# US_IF.net
KiCad netlist of a schematic drawn in Altium Designer
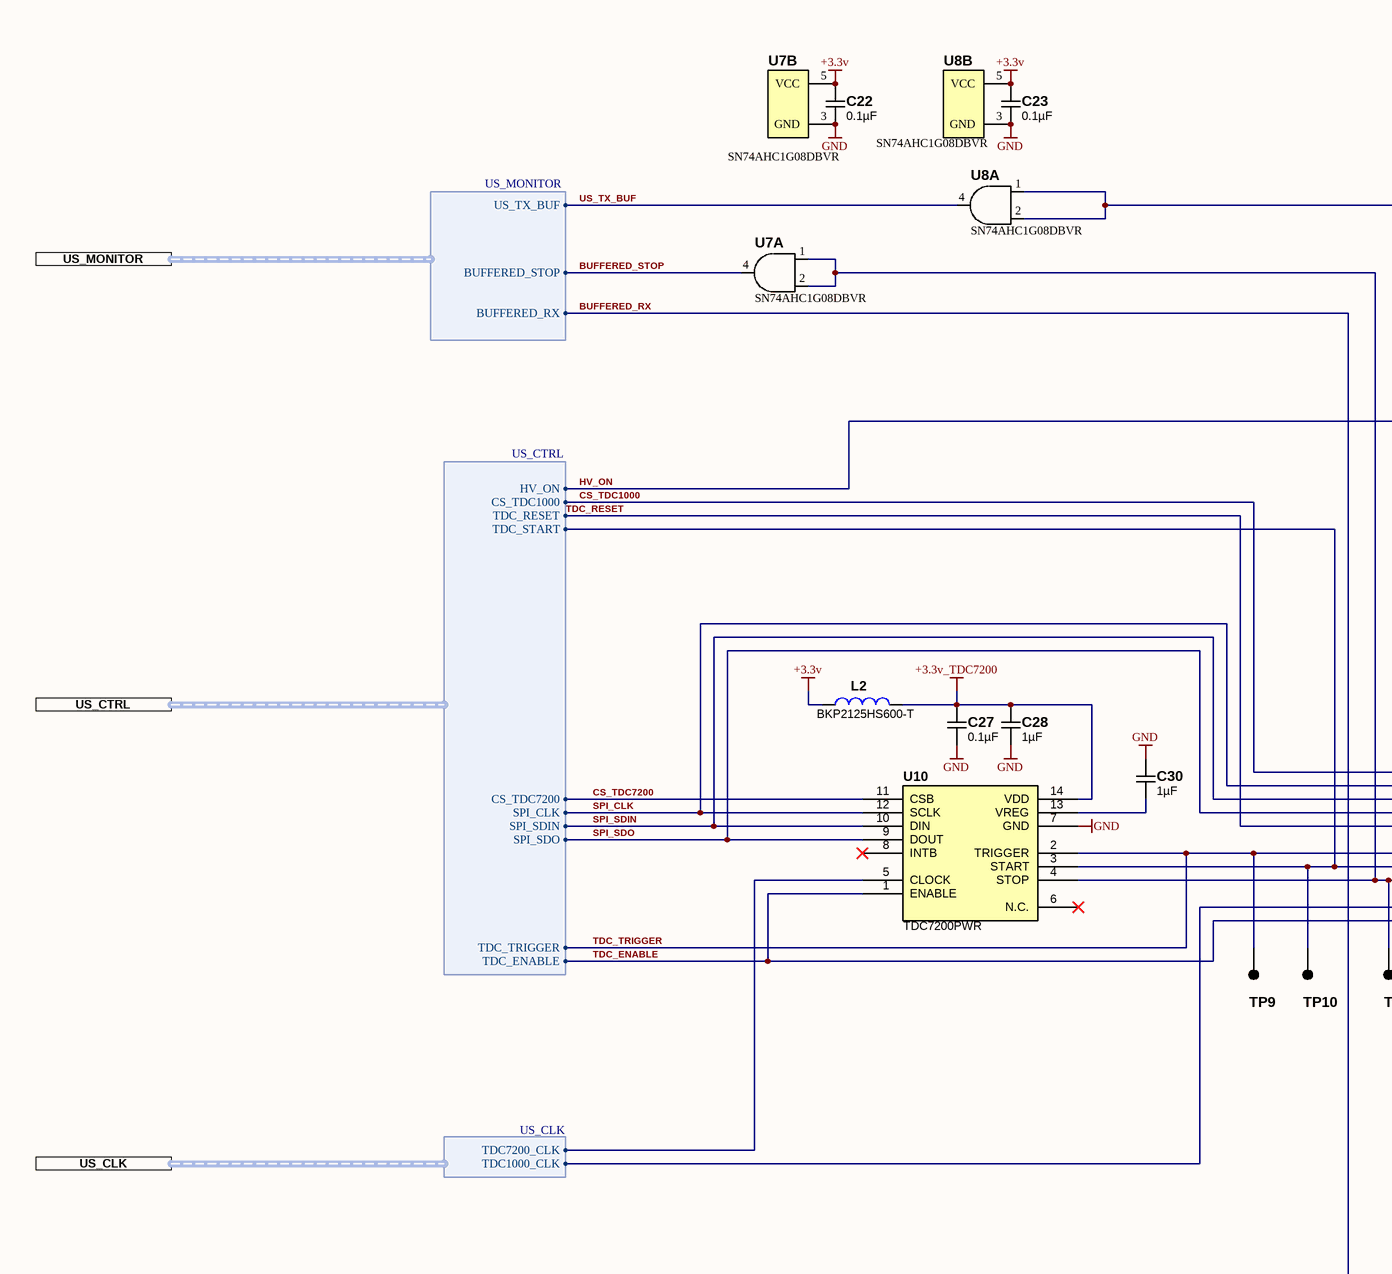
[diagram p0: US_IF.SchDoc, left]
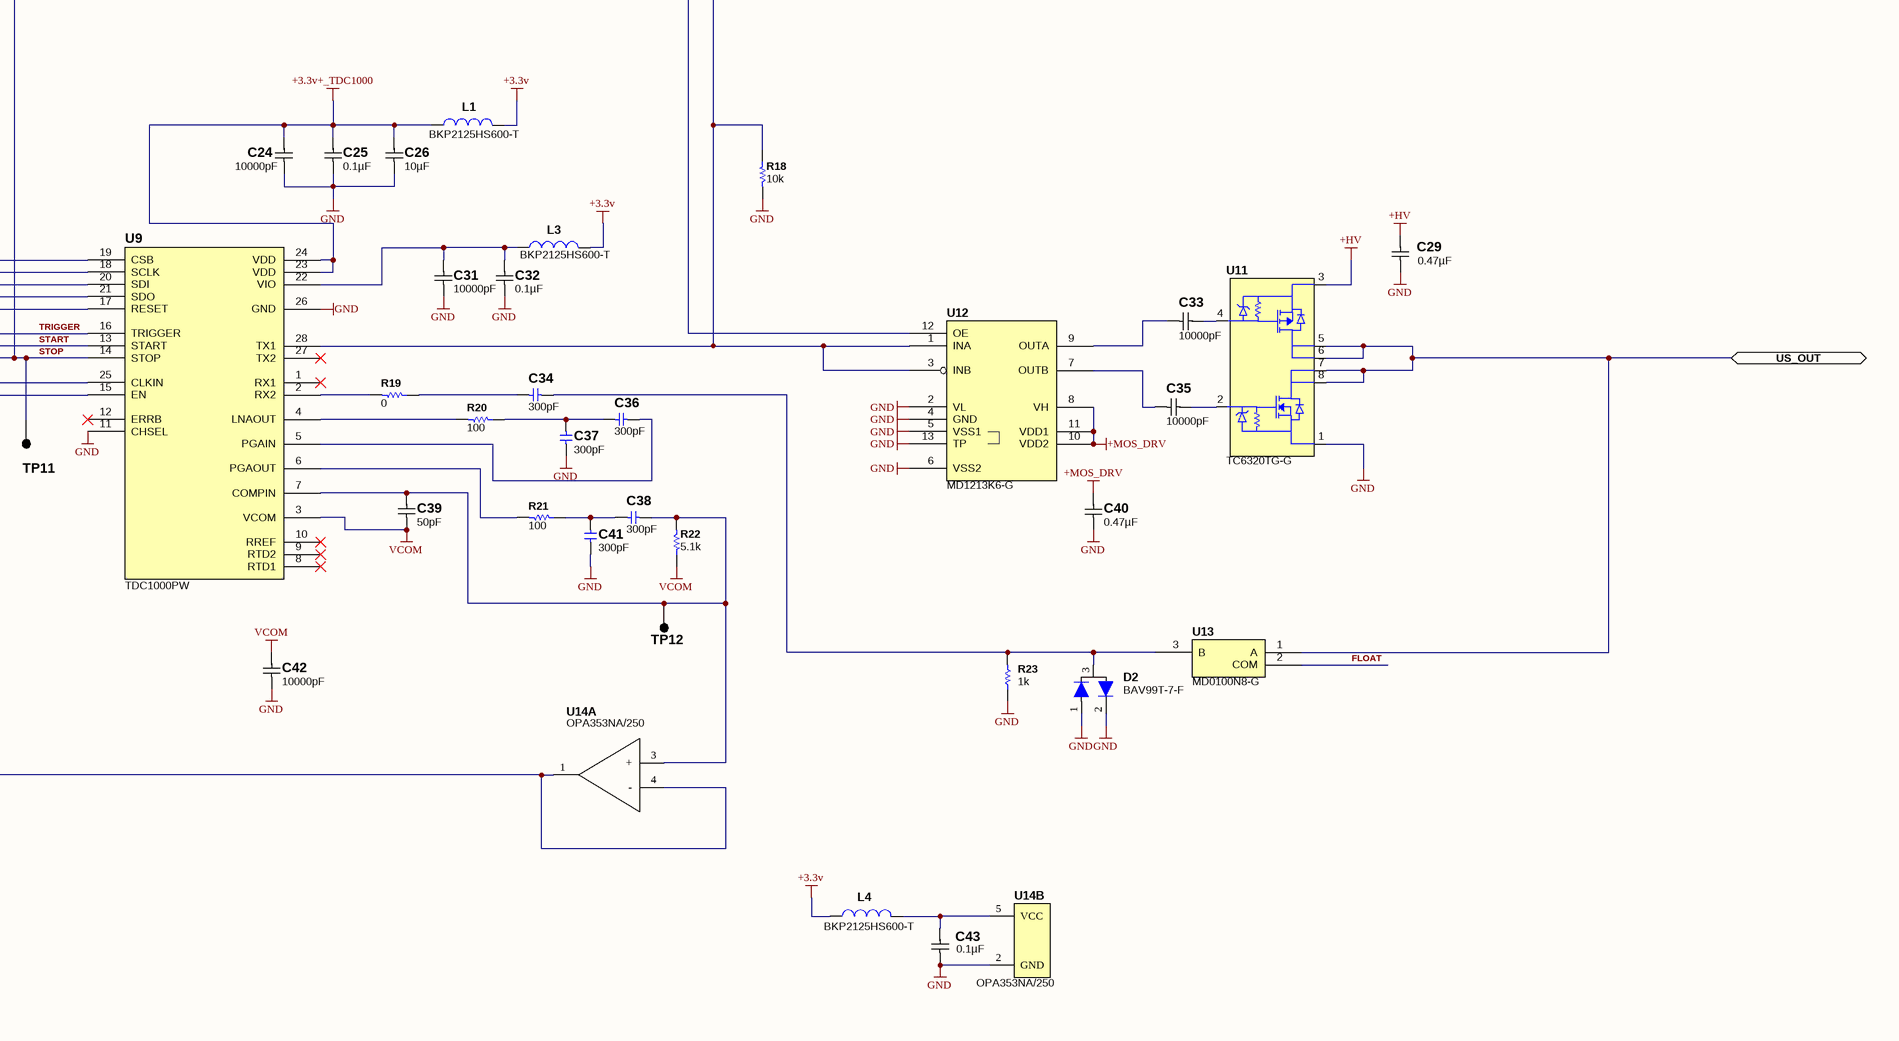
[diagram p1: US_IF.SchDoc, right]

(export (version "E")
  (design (tool "Eeschema 10.0.6"))
  (components
    (comp (ref "C22")
      (value "0.1µF")
      (footprint "C0603_0.90MM_HD")
      (description "CAP CER 0.1UF 50V X7R 0603")
      (fields
        (field (name "MANUFACTURER PART NUMBER") "CGA3E2X7R1H104K080AE")
        (field (name "MANUFACTURER") "TDK Corporation")
      )
      (libsource (lib "Capacitors - TDK- AEC-Q200") (part "C_2P_NP"))
    )
    (comp (ref "C23")
      (value "0.1µF")
      (footprint "C0603_0.90MM_HD")
      (description "CAP CER 0.1UF 50V X7R 0603")
      (fields
        (field (name "MANUFACTURER PART NUMBER") "CGA3E2X7R1H104K080AE")
        (field (name "MANUFACTURER") "TDK Corporation")
      )
      (libsource (lib "Capacitors - TDK- AEC-Q200") (part "C_2P_NP"))
    )
    (comp (ref "C24")
      (value "10000pF")
      (footprint "C0603_0.95MM_HD")
      (description "CAP CER 10000PF 100V C0GNP0 0603")
      (fields
        (field (name "MANUFACTURER PART NUMBER") "CGA3E1C0G2A103J080AE")
        (field (name "MANUFACTURER") "TDK Corporation")
      )
      (libsource (lib "Capacitors - TDK- AEC-Q200") (part "C_2P_NP"))
    )
    (comp (ref "C25")
      (value "0.1µF")
      (footprint "C0603_0.90MM_HD")
      (description "CAP CER 0.1UF 50V X7R 0603")
      (fields
        (field (name "MANUFACTURER PART NUMBER") "CGA3E2X7R1H104K080AE")
        (field (name "MANUFACTURER") "TDK Corporation")
      )
      (libsource (lib "Capacitors - TDK- AEC-Q200") (part "C_2P_NP"))
    )
    (comp (ref "C26")
      (value "10µF")
      (footprint "C0805_1.45MM_HD")
      (description "CAP CER 10UF 6.3V X7R 0805")
      (fields
        (field (name "MANUFACTURER PART NUMBER") "CGA4J1X7R0J106K125AC")
        (field (name "MANUFACTURER") "TDK Corporation")
      )
      (libsource (lib "Capacitors - TDK- AEC-Q200") (part "C_2P_NP"))
    )
    (comp (ref "C27")
      (value "0.1µF")
      (footprint "C0603_0.90MM_HD")
      (description "CAP CER 0.1UF 50V X7R 0603")
      (fields
        (field (name "MANUFACTURER PART NUMBER") "CGA3E2X7R1H104K080AE")
        (field (name "MANUFACTURER") "TDK Corporation")
      )
      (libsource (lib "Capacitors - TDK- AEC-Q200") (part "C_2P_NP"))
    )
    (comp (ref "C28")
      (value "1µF")
      (footprint "C0603_0.95MM_HD")
      (description "CAP CER 1UF 25V X7R 0603")
      (fields
        (field (name "MANUFACTURER PART NUMBER") "CGA3E1X7R1E105K080AE")
        (field (name "MANUFACTURER") "TDK Corporation")
      )
      (libsource (lib "Capacitors - TDK- AEC-Q200") (part "C_2P_NP"))
    )
    (comp (ref "C29")
      (value "0.47µF")
      (footprint "C0805_1.45MM_HD")
      (description "CAP CER 0.47UF 50V X7R 0805")
      (fields
        (field (name "MANUFACTURER PART NUMBER") "CGA4J3X7R1H474K125AE")
        (field (name "MANUFACTURER") "TDK Corporation")
      )
      (libsource (lib "Capacitors - TDK- AEC-Q200") (part "C_2P_NP"))
    )
    (comp (ref "C30")
      (value "1µF")
      (footprint "C0603_0.95MM_HD")
      (description "CAP CER 1UF 25V X7R 0603")
      (fields
        (field (name "MANUFACTURER PART NUMBER") "CGA3E1X7R1E105K080AE")
        (field (name "MANUFACTURER") "TDK Corporation")
      )
      (libsource (lib "Capacitors - TDK- AEC-Q200") (part "C_2P_NP"))
    )
    (comp (ref "C31")
      (value "10000pF")
      (footprint "C0603_0.90MM_HD")
      (description "CAP CER 10000PF 50V X7R 0603")
      (fields
        (field (name "MANUFACTURER PART NUMBER") "CGA3E2X7R1H103M080AE")
        (field (name "MANUFACTURER") "TDK Corporation")
      )
      (libsource (lib "Capacitors - TDK- AEC-Q200") (part "C_2P_NP"))
    )
    (comp (ref "C32")
      (value "0.1µF")
      (footprint "C0603_0.90MM_HD")
      (description "CAP CER 0.1UF 50V X7R 0603")
      (fields
        (field (name "MANUFACTURER PART NUMBER") "CGA3E2X7R1H104K080AE")
        (field (name "MANUFACTURER") "TDK Corporation")
      )
      (libsource (lib "Capacitors - TDK- AEC-Q200") (part "C_2P_NP"))
    )
    (comp (ref "C33")
      (value "10000pF")
      (footprint "C0603_0.95MM_HD")
      (description "CAP CER 10000PF 100V C0GNP0 0603")
      (fields
        (field (name "MANUFACTURER PART NUMBER") "CGA3E1C0G2A103J080AE")
        (field (name "MANUFACTURER") "TDK Corporation")
      )
      (libsource (lib "Capacitors - TDK- AEC-Q200") (part "C_2P_NP"))
    )
    (comp (ref "C34")
      (value "300pF")
      (footprint "C0603_0.90mm_MD")
      (description "Cap Ceramic 300pF 50V C0G 5% SMD 0603 125C Paper T/R")
      (fields
        (field (name "MANUFACTURER PART NUMBER") "CL10C301JB8NNNC")
        (field (name "MANUFACTURER") "Samsung")
      )
      (libsource (lib "eCapacitors") (part "CL10C301JB8NNNC"))
    )
    (comp (ref "C35")
      (value "10000pF")
      (footprint "C0603_0.95MM_HD")
      (description "CAP CER 10000PF 100V C0GNP0 0603")
      (fields
        (field (name "MANUFACTURER PART NUMBER") "CGA3E1C0G2A103J080AE")
        (field (name "MANUFACTURER") "TDK Corporation")
      )
      (libsource (lib "Capacitors - TDK- AEC-Q200") (part "C_2P_NP"))
    )
    (comp (ref "C36")
      (value "300pF")
      (footprint "C0603_0.90mm_MD")
      (description "Cap Ceramic 300pF 50V C0G 5% SMD 0603 125C Paper T/R")
      (fields
        (field (name "MANUFACTURER PART NUMBER") "CL10C301JB8NNNC")
        (field (name "MANUFACTURER") "Samsung")
      )
      (libsource (lib "eCapacitors") (part "CL10C301JB8NNNC"))
    )
    (comp (ref "C37")
      (value "300pF")
      (footprint "C0603_0.90mm_MD")
      (description "Cap Ceramic 300pF 50V C0G 5% SMD 0603 125C Paper T/R")
      (fields
        (field (name "MANUFACTURER PART NUMBER") "CL10C301JB8NNNC")
        (field (name "MANUFACTURER") "Samsung")
      )
      (libsource (lib "eCapacitors") (part "CL10C301JB8NNNC"))
    )
    (comp (ref "C38")
      (value "300pF")
      (footprint "C0603_0.90mm_MD")
      (description "Cap Ceramic 300pF 50V C0G 5% SMD 0603 125C Paper T/R")
      (fields
        (field (name "MANUFACTURER PART NUMBER") "CL10C301JB8NNNC")
        (field (name "MANUFACTURER") "Samsung")
      )
      (libsource (lib "eCapacitors") (part "CL10C301JB8NNNC"))
    )
    (comp (ref "C39")
      (value "50pF")
      (footprint "C0603_0.90MM_HD")
      (description "CAP CER 50PF 100V C0G/NP0 0603")
      (fields
        (field (name "MANUFACTURER PART NUMBER") "CL10C500JC81PNC")
        (field (name "MANUFACTURER") "Samsung Electro-Mechanics")
      )
      (libsource (lib "Capacitors - Samsung - AEC-Q200") (part "C_2P_NP"))
    )
    (comp (ref "C40")
      (value "0.47µF")
      (footprint "C0805_1.45MM_HD")
      (description "CAP CER 0.47UF 50V X7R 0805")
      (fields
        (field (name "MANUFACTURER PART NUMBER") "CGA4J3X7R1H474K125AE")
        (field (name "MANUFACTURER") "TDK Corporation")
      )
      (libsource (lib "Capacitors - TDK- AEC-Q200") (part "C_2P_NP"))
    )
    (comp (ref "C41")
      (value "300pF")
      (footprint "C0603_0.90mm_MD")
      (description "Cap Ceramic 300pF 50V C0G 5% SMD 0603 125C Paper T/R")
      (fields
        (field (name "MANUFACTURER PART NUMBER") "CL10C301JB8NNNC")
        (field (name "MANUFACTURER") "Samsung")
      )
      (libsource (lib "eCapacitors") (part "CL10C301JB8NNNC"))
    )
    (comp (ref "C42")
      (value "10000pF")
      (footprint "C0603_0.95MM_HD")
      (description "CAP CER 10000PF 100V C0GNP0 0603")
      (fields
        (field (name "MANUFACTURER PART NUMBER") "CGA3E1C0G2A103J080AE")
        (field (name "MANUFACTURER") "TDK Corporation")
      )
      (libsource (lib "Capacitors - TDK- AEC-Q200") (part "C_2P_NP"))
    )
    (comp (ref "C43")
      (value "0.1µF")
      (footprint "C0603_0.90MM_HD")
      (description "CAP CER 0.1UF 50V X7R 0603")
      (fields
        (field (name "MANUFACTURER PART NUMBER") "CGA3E2X7R1H104K080AE")
        (field (name "MANUFACTURER") "TDK Corporation")
      )
      (libsource (lib "Capacitors - TDK- AEC-Q200") (part "C_2P_NP"))
    )
    (comp (ref "D2")
      (value "BAV99T-7-F")
      (footprint "D_SOT-523_P")
      (fields (field (name "MANUFACTURER") "Diodes"))
      (libsource (lib "eDiode") (part "BAV99T-7-F"))
    )
    (comp (ref "L1")
      (value "BKP2125HS600-T")
      (footprint "C0805_0.8mm")
      (description "FERRITE BEAD 60 OHM 0805 1LN")
      (fields (field (name "MANUFACTURER") "Taiyo Yuden"))
      (libsource (lib "eInductor") (part "BKP2125HS600-T"))
    )
    (comp (ref "L2")
      (value "BKP2125HS600-T")
      (footprint "C0805_0.8mm")
      (description "FERRITE BEAD 60 OHM 0805 1LN")
      (fields (field (name "MANUFACTURER") "Taiyo Yuden"))
      (libsource (lib "eInductor") (part "BKP2125HS600-T"))
    )
    (comp (ref "L3")
      (value "BKP2125HS600-T")
      (footprint "C0805_0.8mm")
      (description "FERRITE BEAD 60 OHM 0805 1LN")
      (fields (field (name "MANUFACTURER") "Taiyo Yuden"))
      (libsource (lib "eInductor") (part "BKP2125HS600-T"))
    )
    (comp (ref "L4")
      (value "BKP2125HS600-T")
      (footprint "C0805_0.8mm")
      (description "FERRITE BEAD 60 OHM 0805 1LN")
      (fields (field (name "MANUFACTURER") "Taiyo Yuden"))
      (libsource (lib "eInductor") (part "BKP2125HS600-T"))
    )
    (comp (ref "R18")
      (value "10k")
      (footprint "R0603_0.55MM_HD")
      (description "RES 10K OHM 1/10W 1% 0603 SMD")
      (fields
        (field (name "MANUFACTURER PART NUMBER") "ERJ-3EKF1002V")
        (field (name "MANUFACTURER") "Panasonic Electronic Components")
      )
      (libsource (lib "Resistors - Panasonic - AEC-Q200") (part "R_2P"))
    )
    (comp (ref "R19")
      (value "0")
      (footprint "R0603_0.55MM_HD")
      (description "RES 0.0 OHM 1/10W JUMP 0603 SMD")
      (fields
        (field (name "MANUFACTURER PART NUMBER") "ERJ-3GEY0R00V")
        (field (name "MANUFACTURER") "Panasonic Electronic Components")
      )
      (libsource (lib "Resistors - Panasonic - AEC-Q200") (part "R_2P"))
    )
    (comp (ref "R20")
      (value "100")
      (footprint "R0603_0.55MM_HD")
      (description "RES 100 OHM 1/10W 1% 0603 SMD")
      (fields
        (field (name "MANUFACTURER PART NUMBER") "ERJ-3EKF1000V")
        (field (name "MANUFACTURER") "Panasonic Electronic Components")
      )
      (libsource (lib "Resistors - Panasonic - AEC-Q200") (part "R_2P"))
    )
    (comp (ref "R21")
      (value "100")
      (footprint "R0603_0.55MM_HD")
      (description "RES 100 OHM 1/10W 1% 0603 SMD")
      (fields
        (field (name "MANUFACTURER PART NUMBER") "ERJ-3EKF1000V")
        (field (name "MANUFACTURER") "Panasonic Electronic Components")
      )
      (libsource (lib "Resistors - Panasonic - AEC-Q200") (part "R_2P"))
    )
    (comp (ref "R22")
      (value "5.1k")
      (footprint "R0603_0.55MM_HD")
      (description "RES 5.1K OHM 1/10W 1% 0603 SMD")
      (fields
        (field (name "MANUFACTURER PART NUMBER") "ERJ-3EKF5101V")
        (field (name "MANUFACTURER") "Panasonic Electronic Components")
      )
      (libsource (lib "Resistors - Panasonic - AEC-Q200") (part "R_2P"))
    )
    (comp (ref "R23")
      (value "1k")
      (footprint "R0603_0.55MM_HD")
      (description "RES 1K OHM 1/10W 1% 0603 SMD")
      (fields
        (field (name "MANUFACTURER PART NUMBER") "ERJ-3EKF1001V")
        (field (name "MANUFACTURER") "Panasonic Electronic Components")
      )
      (libsource (lib "Resistors - Panasonic - AEC-Q200") (part "R_2P"))
    )
    (comp (ref "TP9")
      (value "SMT_TEST")
      (footprint "SMT_TP - 25")
      (libsource (lib "Hydroscope") (part "SMT_TEST"))
    )
    (comp (ref "TP10")
      (value "SMT_TEST")
      (footprint "SMT_TP - 25")
      (libsource (lib "Hydroscope") (part "SMT_TEST"))
    )
    (comp (ref "TP11")
      (value "SMT_TEST")
      (footprint "SMT_TP - 25")
      (libsource (lib "Hydroscope") (part "SMT_TEST"))
    )
    (comp (ref "TP12")
      (value "SMT_TEST")
      (footprint "SMT_TP - 25")
      (libsource (lib "Hydroscope") (part "SMT_TEST"))
    )
    (comp (ref "U7")
      (value "SN74AHC1G08DBVR")
      (footprint "SOT95P245X145-5L")
      (description "IC SGL 2IN POS-AND GATE SOT23-5")
      (fields (field (name "MANUFACTURER") "Texas Instruments"))
      (libsource (lib "") (part "SN74AHC1G08DBVR_1"))
    )
    (comp (ref "U8")
      (value "SN74AHC1G08DBVR")
      (footprint "SOT95P245X145-5L")
      (description "IC SGL 2IN POS-AND GATE SOT23-5")
      (fields (field (name "MANUFACTURER") "Texas Instruments"))
      (libsource (lib "eIC") (part "SN74AHC1G08DBVR"))
    )
    (comp (ref "U9")
      (value "TDC1000PW")
      (footprint "TSOP65P640X120-28N")
      (description "IC AFE ULTRA SENSING 28TSSOP")
      (fields (field (name "MANUFACTURER") "Texas Instruments"))
      (libsource (lib "eIC") (part "TDC1000PW"))
    )
    (comp (ref "U10")
      (value "TDC7200PWR")
      (footprint "TSSOP14")
      (description "IC DIG CONV 14TSSOP")
      (fields (field (name "MANUFACTURER") "Texas Instruments"))
      (libsource (lib "eIC") (part "TDC7200PWR"))
    )
    (comp (ref "U11")
      (value "TC6320TG-G")
      (footprint "SOIC 8")
      (description "Trans MOSFET N/P-CH 200V 8-Pin SOIC N T/R")
      (fields (field (name "MANUFACTURER") "Microchip Supertex"))
      (libsource (lib "eIC") (part "TC6320TG-G"))
    )
    (comp (ref "U12")
      (value "MD1213K6-G")
      (footprint "QFN80P400X400X100_HS-13N")
      (description "Gate Drivers HI SPD DUAL MOSFET DRIVER")
      (fields (field (name "MANUFACTURER") "Microchip Supertex"))
      (libsource (lib "eIC") (part "MD1213K6-G"))
    )
    (comp (ref "U13")
      (value "MD0100N8-G")
      (footprint "SOT89-150P410X160-3N")
      (description "High Voltage Protection T/R Switch 4-Pin(3+Tab) SOT-89")
      (fields (field (name "MANUFACTURER") "Microchip Supertex"))
      (libsource (lib "eIC") (part "MD0100N8-G"))
    )
    (comp (ref "U14")
      (value "OPA353NA/250")
      (footprint "SOT23-5")
      (description "IC OPAMP GP 44MHZ RRO SOT23-5")
      (fields (field (name "MANUFACTURER") "Texas Instruments"))
      (libsource (lib "eOPAMP") (part "OPA353NA/250"))
    )
  )
  (nets
    (net (code "4") (name "+3.3v") (class "Default")
      (node (ref "C22") (pin "2") (pinfunction "1_2") (pintype "passive"))
      (node (ref "C23") (pin "2") (pinfunction "1_2") (pintype "passive"))
      (node (ref "L1") (pin "1") (pinfunction "1_1") (pintype "passive"))
      (node (ref "L2") (pin "2") (pinfunction "2_2") (pintype "passive"))
      (node (ref "L3") (pin "1") (pinfunction "1_1") (pintype "passive"))
      (node (ref "L4") (pin "2") (pinfunction "2_2") (pintype "passive"))
      (node (ref "U7") (pin "5") (pinfunction "VCC_5") (pintype "passive"))
      (node (ref "U8") (pin "5") (pinfunction "VCC_5") (pintype "passive"))
    )
    (net (code "5") (name "+3.3v+_TDC1000") (class "Default")
      (node (ref "C24") (pin "2") (pinfunction "1_2") (pintype "passive"))
      (node (ref "C25") (pin "2") (pinfunction "1_2") (pintype "passive"))
      (node (ref "C26") (pin "2") (pinfunction "1_2") (pintype "passive"))
      (node (ref "L1") (pin "2") (pinfunction "2_2") (pintype "passive"))
      (node (ref "U9") (pin "23") (pinfunction "VDD_23") (pintype "passive"))
      (node (ref "U9") (pin "24") (pinfunction "VDD_24") (pintype "passive"))
    )
    (net (code "6") (name "+3.3v_TDC7200") (class "Default")
      (node (ref "C27") (pin "2") (pinfunction "1_2") (pintype "passive"))
      (node (ref "C28") (pin "2") (pinfunction "1_2") (pintype "passive"))
      (node (ref "L2") (pin "1") (pinfunction "1_1") (pintype "passive"))
      (node (ref "U10") (pin "14") (pinfunction "VDD_14") (pintype "passive"))
    )
    (net (code "7") (name "+HV") (class "Default")
      (node (ref "C29") (pin "2") (pinfunction "1_2") (pintype "passive"))
      (node (ref "U11") (pin "3") (pinfunction "SP_3") (pintype "passive"))
    )
    (net (code "8") (name "+MOS_DRV") (class "Default")
      (node (ref "C40") (pin "2") (pinfunction "1_2") (pintype "passive"))
      (node (ref "U12") (pin "10") (pinfunction "VDD2_10") (pintype "passive"))
      (node (ref "U12") (pin "11") (pinfunction "VDD1_11") (pintype "passive"))
      (node (ref "U12") (pin "8") (pinfunction "VH_8") (pintype "passive"))
    )
    (net (code "9") (name "/BUFFERED_RX") (class "Default")
      (node (ref "U14") (pin "1") (pinfunction "OUT_1") (pintype "passive"))
      (node (ref "U14") (pin "4") (pinfunction "-_4") (pintype "passive"))
    )
    (net (code "10") (name "/BUFFERED_STOP") (class "Default")
      (node (ref "U7") (pin "4") (pinfunction "OUT_4") (pintype "passive"))
    )
    (net (code "11") (name "/CS_TDC1000") (class "Default")
      (node (ref "U9") (pin "19") (pinfunction "CSB_19") (pintype "passive"))
    )
    (net (code "12") (name "/CS_TDC7200") (class "Default")
      (node (ref "U10") (pin "11") (pinfunction "CSB_11") (pintype "passive"))
    )
    (net (code "13") (name "/FLOAT") (class "Default")
      (node (ref "U13") (pin "2") (pinfunction "COM_2") (pintype "passive"))
    )
    (net (code "14") (name "/HV_ON") (class "Default")
      (node (ref "U12") (pin "12") (pinfunction "OE_12") (pintype "passive"))
    )
    (net (code "15") (name "/SPI_CLK") (class "Default")
      (node (ref "U10") (pin "12") (pinfunction "SCLK_12") (pintype "passive"))
      (node (ref "U9") (pin "18") (pinfunction "SCLK_18") (pintype "passive"))
    )
    (net (code "16") (name "/SPI_SDIN") (class "Default")
      (node (ref "U10") (pin "10") (pinfunction "DIN_10") (pintype "passive"))
      (node (ref "U9") (pin "20") (pinfunction "SDI_20") (pintype "passive"))
    )
    (net (code "17") (name "/SPI_SDO") (class "Default")
      (node (ref "U10") (pin "9") (pinfunction "DOUT_9") (pintype "passive"))
      (node (ref "U9") (pin "21") (pinfunction "SDO_21") (pintype "passive"))
    )
    (net (code "18") (name "/START") (class "Default")
      (node (ref "TP10") (pin "1") (pinfunction "1_1") (pintype "passive"))
      (node (ref "U10") (pin "3") (pinfunction "START_3") (pintype "passive"))
      (node (ref "U9") (pin "13") (pinfunction "START_13") (pintype "passive"))
    )
    (net (code "19") (name "/STOP") (class "Default")
      (node (ref "TP11") (pin "1") (pinfunction "1_1") (pintype "passive"))
      (node (ref "U10") (pin "4") (pinfunction "STOP_4") (pintype "passive"))
      (node (ref "U7") (pin "1") (pinfunction "A_1") (pintype "passive"))
      (node (ref "U7") (pin "2") (pinfunction "B_2") (pintype "passive"))
      (node (ref "U9") (pin "14") (pinfunction "STOP_14") (pintype "passive"))
    )
    (net (code "20") (name "/TDC1000_CLK") (class "Default")
      (node (ref "U9") (pin "25") (pinfunction "CLKIN_25") (pintype "passive"))
    )
    (net (code "21") (name "/TDC7200_CLK") (class "Default")
      (node (ref "U10") (pin "5") (pinfunction "CLOCK_5") (pintype "passive"))
    )
    (net (code "22") (name "/TDC_ENABLE") (class "Default")
      (node (ref "U10") (pin "1") (pinfunction "ENABLE_1") (pintype "passive"))
      (node (ref "U9") (pin "15") (pinfunction "EN_15") (pintype "passive"))
    )
    (net (code "23") (name "/TDC_RESET") (class "Default")
      (node (ref "U9") (pin "17") (pinfunction "RESET_17") (pintype "passive"))
    )
    (net (code "24") (name "/TDC_TRIGGER") (class "Default")
      (node (ref "TP9") (pin "1") (pinfunction "1_1") (pintype "passive"))
      (node (ref "U10") (pin "2") (pinfunction "TRIGGER_2") (pintype "passive"))
      (node (ref "U9") (pin "16") (pinfunction "TRIGGER_16") (pintype "passive"))
    )
    (net (code "25") (name "/US_OUT") (class "Default")
      (node (ref "U11") (pin "5") (pinfunction "DN_5") (pintype "passive"))
      (node (ref "U11") (pin "6") (pinfunction "DN_6") (pintype "passive"))
      (node (ref "U11") (pin "7") (pinfunction "DP_7") (pintype "passive"))
      (node (ref "U11") (pin "8") (pinfunction "DP_8") (pintype "passive"))
      (node (ref "U13") (pin "1") (pinfunction "A_1") (pintype "passive"))
    )
    (net (code "26") (name "/US_TX_BUF") (class "Default")
      (node (ref "U8") (pin "4") (pinfunction "OUT_4") (pintype "passive"))
    )
    (net (code "30") (name "GND") (class "Default")
      (node (ref "C22") (pin "1") (pinfunction "1_1") (pintype "passive"))
      (node (ref "C23") (pin "1") (pinfunction "1_1") (pintype "passive"))
      (node (ref "C24") (pin "1") (pinfunction "1_1") (pintype "passive"))
      (node (ref "C25") (pin "1") (pinfunction "1_1") (pintype "passive"))
      (node (ref "C26") (pin "1") (pinfunction "1_1") (pintype "passive"))
      (node (ref "C27") (pin "1") (pinfunction "1_1") (pintype "passive"))
      (node (ref "C28") (pin "1") (pinfunction "1_1") (pintype "passive"))
      (node (ref "C29") (pin "1") (pinfunction "1_1") (pintype "passive"))
      (node (ref "C30") (pin "2") (pinfunction "1_2") (pintype "passive"))
      (node (ref "C31") (pin "1") (pinfunction "1_1") (pintype "passive"))
      (node (ref "C32") (pin "1") (pinfunction "1_1") (pintype "passive"))
      (node (ref "C37") (pin "1") (pinfunction "1_1") (pintype "passive"))
      (node (ref "C40") (pin "1") (pinfunction "1_1") (pintype "passive"))
      (node (ref "C41") (pin "2") (pinfunction "2_2") (pintype "passive"))
      (node (ref "C42") (pin "1") (pinfunction "1_1") (pintype "passive"))
      (node (ref "C43") (pin "1") (pinfunction "1_1") (pintype "passive"))
      (node (ref "D2") (pin "1") (pinfunction "A_1") (pintype "passive"))
      (node (ref "D2") (pin "2") (pinfunction "C_2") (pintype "passive"))
      (node (ref "R18") (pin "2") (pinfunction "2_2") (pintype "passive"))
      (node (ref "R23") (pin "1") (pinfunction "1_1") (pintype "passive"))
      (node (ref "U10") (pin "7") (pinfunction "GND_7") (pintype "passive"))
      (node (ref "U11") (pin "1") (pinfunction "SN_1") (pintype "passive"))
      (node (ref "U12") (pin "13") (pinfunction "TP_13") (pintype "passive"))
      (node (ref "U12") (pin "2") (pinfunction "VL_2") (pintype "passive"))
      (node (ref "U12") (pin "4") (pinfunction "GND_4") (pintype "passive"))
      (node (ref "U12") (pin "5") (pinfunction "VSS1_5") (pintype "passive"))
      (node (ref "U12") (pin "6") (pinfunction "VSS2_6") (pintype "passive"))
      (node (ref "U14") (pin "2") (pinfunction "GND_2") (pintype "passive"))
      (node (ref "U7") (pin "3") (pinfunction "GND_3") (pintype "passive"))
      (node (ref "U8") (pin "3") (pinfunction "GND_3") (pintype "passive"))
      (node (ref "U9") (pin "11") (pinfunction "CHSEL_11") (pintype "passive"))
      (node (ref "U9") (pin "26") (pinfunction "GND_26") (pintype "passive"))
    )
    (net (code "31") (name "Net-(C34-Pad2)") (class "Default")
      (node (ref "C34") (pin "2") (pinfunction "2_2") (pintype "passive"))
      (node (ref "R19") (pin "1") (pinfunction "1_1") (pintype "passive"))
    )
    (net (code "32") (name "Net-(C36-Pad2)") (class "Default")
      (node (ref "C36") (pin "2") (pinfunction "2_2") (pintype "passive"))
      (node (ref "C37") (pin "2") (pinfunction "2_2") (pintype "passive"))
      (node (ref "R20") (pin "1") (pinfunction "1_1") (pintype "passive"))
    )
    (net (code "33") (name "Net-(C38-Pad1)") (class "Default")
      (node (ref "C38") (pin "1") (pinfunction "1_1") (pintype "passive"))
      (node (ref "C41") (pin "1") (pinfunction "1_1") (pintype "passive"))
      (node (ref "R21") (pin "1") (pinfunction "1_1") (pintype "passive"))
    )
    (net (code "34") (name "Net-(D2-AC)") (class "Default")
      (node (ref "C34") (pin "1") (pinfunction "1_1") (pintype "passive"))
      (node (ref "D2") (pin "3") (pinfunction "AC_3") (pintype "passive"))
      (node (ref "R23") (pin "2") (pinfunction "2_2") (pintype "passive"))
      (node (ref "U13") (pin "3") (pinfunction "B_3") (pintype "passive"))
    )
    (net (code "35") (name "Net-(U9-LNAOUT)") (class "Default")
      (node (ref "R20") (pin "2") (pinfunction "2_2") (pintype "passive"))
      (node (ref "U9") (pin "4") (pinfunction "LNAOUT_4") (pintype "passive"))
    )
    (net (code "36") (name "Net-(U9-PGAIN)") (class "Default")
      (node (ref "C36") (pin "1") (pinfunction "1_1") (pintype "passive"))
      (node (ref "U9") (pin "5") (pinfunction "PGAIN_5") (pintype "passive"))
    )
    (net (code "37") (name "Net-(U9-PGAOUT)") (class "Default")
      (node (ref "R21") (pin "2") (pinfunction "2_2") (pintype "passive"))
      (node (ref "U9") (pin "6") (pinfunction "PGAOUT_6") (pintype "passive"))
    )
    (net (code "38") (name "Net-(U9-RX2)") (class "Default")
      (node (ref "R19") (pin "2") (pinfunction "2_2") (pintype "passive"))
      (node (ref "U9") (pin "2") (pinfunction "RX2_2") (pintype "passive"))
    )
    (net (code "39") (name "Net-(U9-VIO)") (class "Default")
      (node (ref "C31") (pin "2") (pinfunction "1_2") (pintype "passive"))
      (node (ref "C32") (pin "2") (pinfunction "1_2") (pintype "passive"))
      (node (ref "L3") (pin "2") (pinfunction "2_2") (pintype "passive"))
      (node (ref "U9") (pin "22") (pinfunction "VIO_22") (pintype "passive"))
    )
    (net (code "40") (name "Net-(U10-VREG)") (class "Default")
      (node (ref "C30") (pin "1") (pinfunction "1_1") (pintype "passive"))
      (node (ref "U10") (pin "13") (pinfunction "VREG_13") (pintype "passive"))
    )
    (net (code "41") (name "Net-(U11-GN)") (class "Default")
      (node (ref "C35") (pin "2") (pinfunction "1_2") (pintype "passive"))
      (node (ref "U11") (pin "2") (pinfunction "GN_2") (pintype "passive"))
    )
    (net (code "42") (name "Net-(U11-GP)") (class "Default")
      (node (ref "C33") (pin "2") (pinfunction "1_2") (pintype "passive"))
      (node (ref "U11") (pin "4") (pinfunction "GP_4") (pintype "passive"))
    )
    (net (code "43") (name "Net-(U12-INA)") (class "Default")
      (node (ref "R18") (pin "1") (pinfunction "1_1") (pintype "passive"))
      (node (ref "U12") (pin "1") (pinfunction "INA_1") (pintype "passive"))
      (node (ref "U12") (pin "3") (pinfunction "INB_3") (pintype "passive"))
      (node (ref "U8") (pin "1") (pinfunction "A_1") (pintype "passive"))
      (node (ref "U8") (pin "2") (pinfunction "B_2") (pintype "passive"))
      (node (ref "U9") (pin "28") (pinfunction "TX1_28") (pintype "passive"))
    )
    (net (code "44") (name "Net-(U12-OUTA)") (class "Default")
      (node (ref "C33") (pin "1") (pinfunction "1_1") (pintype "passive"))
      (node (ref "U12") (pin "9") (pinfunction "OUTA_9") (pintype "passive"))
    )
    (net (code "45") (name "Net-(U12-OUTB)") (class "Default")
      (node (ref "C35") (pin "1") (pinfunction "1_1") (pintype "passive"))
      (node (ref "U12") (pin "7") (pinfunction "OUTB_7") (pintype "passive"))
    )
    (net (code "46") (name "Net-(U14A-+)") (class "Default")
      (node (ref "C38") (pin "2") (pinfunction "2_2") (pintype "passive"))
      (node (ref "C39") (pin "2") (pinfunction "1_2") (pintype "passive"))
      (node (ref "R22") (pin "2") (pinfunction "2_2") (pintype "passive"))
      (node (ref "TP12") (pin "1") (pinfunction "1_1") (pintype "passive"))
      (node (ref "U14") (pin "3") (pinfunction "+_3") (pintype "passive"))
      (node (ref "U9") (pin "7") (pinfunction "COMPIN_7") (pintype "passive"))
    )
    (net (code "47") (name "Net-(U14B-VCC)") (class "Default")
      (node (ref "C43") (pin "2") (pinfunction "1_2") (pintype "passive"))
      (node (ref "L4") (pin "1") (pinfunction "1_1") (pintype "passive"))
      (node (ref "U14") (pin "5") (pinfunction "VCC_5") (pintype "passive"))
    )
    (net (code "48") (name "VCOM") (class "Default")
      (node (ref "C39") (pin "1") (pinfunction "1_1") (pintype "passive"))
      (node (ref "C42") (pin "2") (pinfunction "1_2") (pintype "passive"))
      (node (ref "R22") (pin "1") (pinfunction "1_1") (pintype "passive"))
      (node (ref "U9") (pin "3") (pinfunction "VCOM_3") (pintype "passive"))
    )
    (net (code "49") (name "unconnected-(U9-ERRB-Pad12)") (class "Default")
      (node (ref "U9") (pin "12") (pinfunction "ERRB_12") (pintype "passive+no_connect"))
    )
    (net (code "50") (name "unconnected-(U9-RREF-Pad10)") (class "Default")
      (node (ref "U9") (pin "10") (pinfunction "RREF_10") (pintype "passive+no_connect"))
    )
    (net (code "51") (name "unconnected-(U9-RTD1-Pad8)") (class "Default")
      (node (ref "U9") (pin "8") (pinfunction "RTD1_8") (pintype "passive+no_connect"))
    )
    (net (code "52") (name "unconnected-(U9-RTD2-Pad9)") (class "Default")
      (node (ref "U9") (pin "9") (pinfunction "RTD2_9") (pintype "passive+no_connect"))
    )
    (net (code "53") (name "unconnected-(U9-RX1-Pad1)") (class "Default")
      (node (ref "U9") (pin "1") (pinfunction "RX1_1") (pintype "passive+no_connect"))
    )
    (net (code "54") (name "unconnected-(U9-TX2-Pad27)") (class "Default")
      (node (ref "U9") (pin "27") (pinfunction "TX2_27") (pintype "passive+no_connect"))
    )
    (net (code "55") (name "unconnected-(U10-INTB-Pad8)") (class "Default")
      (node (ref "U10") (pin "8") (pinfunction "INTB_8") (pintype "passive+no_connect"))
    )
    (net (code "56") (name "unconnected-(U10-N.C.-Pad6)") (class "Default")
      (node (ref "U10") (pin "6") (pinfunction "N.C._6") (pintype "passive+no_connect"))
    )
  )
)
